# max522.net
KiCad netlist of a schematic drawn in EAGLE
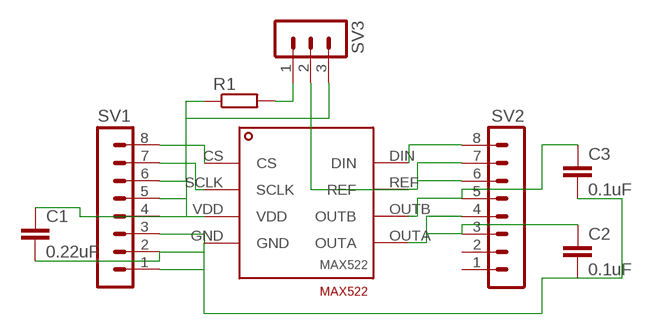
[diagram p0: schematic, sheet 1]

(export (version "E")
  (design (tool "Eeschema 10.0.6"))
  (components
    (comp (ref "C1")
      (value "0.22uF")
      (footprint "eagle-import:C0805")
      (libsource (lib "eagle-import") (part "C-EUC0805"))
    )
    (comp (ref "C2")
      (value "0.1uF")
      (footprint "eagle-import:C0805")
      (libsource (lib "eagle-import") (part "C-EUC0805"))
    )
    (comp (ref "C3")
      (value "0.1uF")
      (footprint "eagle-import:C0805")
      (libsource (lib "eagle-import") (part "C-EUC0805"))
    )
    (comp (ref "R1")
      (value "R-EU_M0805")
      (footprint "eagle-import:M0805")
      (libsource (lib "eagle-import") (part "R-EU_M0805"))
    )
    (comp (ref "SV1")
      (value "MA08-1")
      (footprint "eagle-import:MA08-1")
      (libsource (lib "eagle-import") (part "MA08-1"))
    )
    (comp (ref "SV2")
      (value "MA08-1")
      (footprint "eagle-import:MA08-1")
      (libsource (lib "eagle-import") (part "MA08-1"))
    )
    (comp (ref "SV3")
      (value "MA03-1")
      (footprint "eagle-import:MA03-1")
      (libsource (lib "eagle-import") (part "MA03-1"))
    )
    (comp (ref "U$1")
      (value "MAX522")
      (footprint "eagle-import:MAX522")
      (libsource (lib "eagle-import") (part "MAX522"))
    )
  )
  (nets
    (net (code "1") (name "Net-(C1-Pad1)") (class "Default")
      (node (ref "C1") (pin "1") (pinfunction "1_1") (pintype "passive"))
      (node (ref "R1") (pin "1") (pinfunction "1_1") (pintype "passive"))
      (node (ref "SV1") (pin "4") (pinfunction "4_4") (pintype "passive"))
      (node (ref "SV1") (pin "5") (pinfunction "5_5") (pintype "passive"))
      (node (ref "SV1") (pin "6") (pinfunction "6_6") (pintype "passive"))
      (node (ref "SV3") (pin "3") (pinfunction "3_3") (pintype "passive"))
      (node (ref "U$1") (pin "VDD") (pinfunction "VDD_VDD") (pintype "power_in"))
    )
    (net (code "2") (name "Net-(C1-Pad2)") (class "Default")
      (node (ref "C1") (pin "2") (pinfunction "2_2") (pintype "passive"))
      (node (ref "C2") (pin "2") (pinfunction "2_2") (pintype "passive"))
      (node (ref "C3") (pin "2") (pinfunction "2_2") (pintype "passive"))
      (node (ref "SV1") (pin "1") (pinfunction "1_1") (pintype "passive"))
      (node (ref "SV1") (pin "2") (pinfunction "2_2") (pintype "passive"))
      (node (ref "SV1") (pin "3") (pinfunction "3_3") (pintype "passive"))
      (node (ref "U$1") (pin "GND") (pinfunction "GND_GND") (pintype "power_in"))
    )
    (net (code "3") (name "Net-(C2-Pad1)") (class "Default")
      (node (ref "C2") (pin "1") (pinfunction "1_1") (pintype "passive"))
      (node (ref "SV2") (pin "3") (pinfunction "3_3") (pintype "passive"))
      (node (ref "SV2") (pin "4") (pinfunction "4_4") (pintype "passive"))
      (node (ref "U$1") (pin "OUTA") (pinfunction "OUTA_OUTA") (pintype "output"))
    )
    (net (code "4") (name "Net-(C3-Pad1)") (class "Default")
      (node (ref "C3") (pin "1") (pinfunction "1_1") (pintype "passive"))
      (node (ref "SV2") (pin "5") (pinfunction "5_5") (pintype "passive"))
      (node (ref "U$1") (pin "OUTB") (pinfunction "OUTB_OUTB") (pintype "output"))
    )
    (net (code "5") (name "Net-(R1-Pad2)") (class "Default")
      (node (ref "R1") (pin "2") (pinfunction "2_2") (pintype "passive"))
      (node (ref "SV3") (pin "1") (pinfunction "1_1") (pintype "passive"))
    )
    (net (code "6") (name "Net-(SV1-Pad7)") (class "Default")
      (node (ref "SV1") (pin "7") (pinfunction "7_7") (pintype "passive"))
      (node (ref "U$1") (pin "SCLK") (pinfunction "SCLK_SCLK") (pintype "input"))
    )
    (net (code "7") (name "Net-(SV1-Pad8)") (class "Default")
      (node (ref "SV1") (pin "8") (pinfunction "8_8") (pintype "passive"))
      (node (ref "U$1") (pin "CS") (pinfunction "CS_CS") (pintype "input"))
    )
    (net (code "8") (name "Net-(SV2-Pad6)") (class "Default")
      (node (ref "SV2") (pin "6") (pinfunction "6_6") (pintype "passive"))
      (node (ref "SV2") (pin "7") (pinfunction "7_7") (pintype "passive"))
      (node (ref "SV3") (pin "2") (pinfunction "2_2") (pintype "passive"))
      (node (ref "U$1") (pin "REF") (pinfunction "REF_REF") (pintype "power_in"))
    )
    (net (code "9") (name "Net-(SV2-Pad8)") (class "Default")
      (node (ref "SV2") (pin "8") (pinfunction "8_8") (pintype "passive"))
      (node (ref "U$1") (pin "DIN") (pinfunction "DIN_DIN") (pintype "input"))
    )
    (net (code "10") (name "unconnected-(SV2-Pad1)") (class "Default")
      (node (ref "SV2") (pin "1") (pinfunction "1_1") (pintype "passive"))
    )
    (net (code "11") (name "unconnected-(SV2-Pad2)") (class "Default")
      (node (ref "SV2") (pin "2") (pinfunction "2_2") (pintype "passive"))
    )
  )
)
